# 4brar07_ESP8266.net
KiCad netlist of a schematic drawn in EAGLE
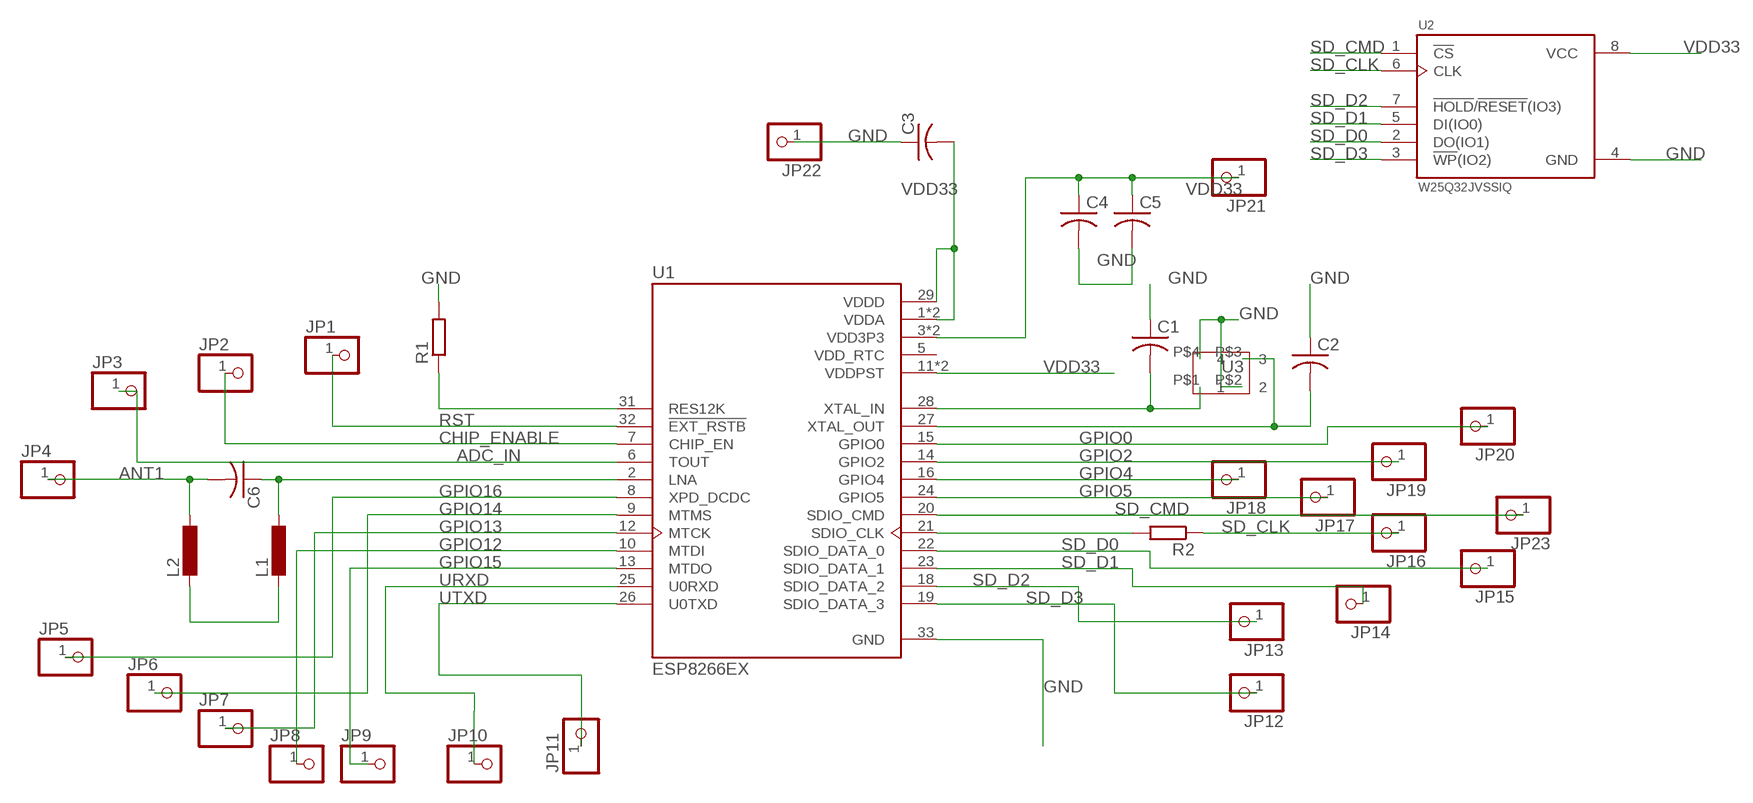
[diagram p0: schematic, sheet 1]

(export (version "E")
  (design (tool "Eeschema 10.0.6"))
  (components
    (comp (ref "C1")
      (value "C-USC0805")
      (footprint "eagle-import:C0805")
      (libsource (lib "eagle-import") (part "C-USC0805"))
    )
    (comp (ref "C2")
      (value "C-USC0805")
      (footprint "eagle-import:C0805")
      (libsource (lib "eagle-import") (part "C-USC0805"))
    )
    (comp (ref "C3")
      (value "C-USC0805")
      (footprint "eagle-import:C0805")
      (libsource (lib "eagle-import") (part "C-USC0805"))
    )
    (comp (ref "C4")
      (value "C-USC0805")
      (footprint "eagle-import:C0805")
      (libsource (lib "eagle-import") (part "C-USC0805"))
    )
    (comp (ref "C5")
      (value "C-USC0805")
      (footprint "eagle-import:C0805")
      (libsource (lib "eagle-import") (part "C-USC0805"))
    )
    (comp (ref "C6")
      (value "C-USC0805")
      (footprint "eagle-import:C0805")
      (libsource (lib "eagle-import") (part "C-USC0805"))
    )
    (comp (ref "JP1")
      (value "PINHD-1X1")
      (footprint "eagle-import:1X01")
      (libsource (lib "eagle-import") (part "PINHD-1X1"))
    )
    (comp (ref "JP2")
      (value "PINHD-1X1")
      (footprint "eagle-import:1X01")
      (libsource (lib "eagle-import") (part "PINHD-1X1"))
    )
    (comp (ref "JP3")
      (value "PINHD-1X1")
      (footprint "eagle-import:1X01")
      (libsource (lib "eagle-import") (part "PINHD-1X1"))
    )
    (comp (ref "JP4")
      (value "PINHD-1X1")
      (footprint "eagle-import:1X01")
      (libsource (lib "eagle-import") (part "PINHD-1X1"))
    )
    (comp (ref "JP5")
      (value "PINHD-1X1")
      (footprint "eagle-import:1X01")
      (libsource (lib "eagle-import") (part "PINHD-1X1"))
    )
    (comp (ref "JP6")
      (value "PINHD-1X1")
      (footprint "eagle-import:1X01")
      (libsource (lib "eagle-import") (part "PINHD-1X1"))
    )
    (comp (ref "JP7")
      (value "PINHD-1X1")
      (footprint "eagle-import:1X01")
      (libsource (lib "eagle-import") (part "PINHD-1X1"))
    )
    (comp (ref "JP8")
      (value "PINHD-1X1")
      (footprint "eagle-import:1X01")
      (libsource (lib "eagle-import") (part "PINHD-1X1"))
    )
    (comp (ref "JP9")
      (value "PINHD-1X1")
      (footprint "eagle-import:1X01")
      (libsource (lib "eagle-import") (part "PINHD-1X1"))
    )
    (comp (ref "JP10")
      (value "PINHD-1X1")
      (footprint "eagle-import:1X01")
      (libsource (lib "eagle-import") (part "PINHD-1X1"))
    )
    (comp (ref "JP11")
      (value "PINHD-1X1")
      (footprint "eagle-import:1X01")
      (libsource (lib "eagle-import") (part "PINHD-1X1"))
    )
    (comp (ref "JP12")
      (value "PINHD-1X1")
      (footprint "eagle-import:1X01")
      (libsource (lib "eagle-import") (part "PINHD-1X1"))
    )
    (comp (ref "JP13")
      (value "PINHD-1X1")
      (footprint "eagle-import:1X01")
      (libsource (lib "eagle-import") (part "PINHD-1X1"))
    )
    (comp (ref "JP14")
      (value "PINHD-1X1")
      (footprint "eagle-import:1X01")
      (libsource (lib "eagle-import") (part "PINHD-1X1"))
    )
    (comp (ref "JP15")
      (value "PINHD-1X1")
      (footprint "eagle-import:1X01")
      (libsource (lib "eagle-import") (part "PINHD-1X1"))
    )
    (comp (ref "JP16")
      (value "PINHD-1X1")
      (footprint "eagle-import:1X01")
      (libsource (lib "eagle-import") (part "PINHD-1X1"))
    )
    (comp (ref "JP17")
      (value "PINHD-1X1")
      (footprint "eagle-import:1X01")
      (libsource (lib "eagle-import") (part "PINHD-1X1"))
    )
    (comp (ref "JP18")
      (value "PINHD-1X1")
      (footprint "eagle-import:1X01")
      (libsource (lib "eagle-import") (part "PINHD-1X1"))
    )
    (comp (ref "JP19")
      (value "PINHD-1X1")
      (footprint "eagle-import:1X01")
      (libsource (lib "eagle-import") (part "PINHD-1X1"))
    )
    (comp (ref "JP20")
      (value "PINHD-1X1")
      (footprint "eagle-import:1X01")
      (libsource (lib "eagle-import") (part "PINHD-1X1"))
    )
    (comp (ref "JP21")
      (value "PINHD-1X1")
      (footprint "eagle-import:1X01")
      (libsource (lib "eagle-import") (part "PINHD-1X1"))
    )
    (comp (ref "JP22")
      (value "PINHD-1X1")
      (footprint "eagle-import:1X01")
      (libsource (lib "eagle-import") (part "PINHD-1X1"))
    )
    (comp (ref "JP23")
      (value "PINHD-1X1")
      (footprint "eagle-import:1X01")
      (libsource (lib "eagle-import") (part "PINHD-1X1"))
    )
    (comp (ref "L1")
      (value "L-EUL1812")
      (footprint "eagle-import:L1812")
      (libsource (lib "eagle-import") (part "L-EUL1812"))
    )
    (comp (ref "L2")
      (value "L-EUL1812")
      (footprint "eagle-import:L1812")
      (libsource (lib "eagle-import") (part "L-EUL1812"))
    )
    (comp (ref "R1")
      (value "R-EU_R0805")
      (footprint "eagle-import:R0805")
      (libsource (lib "eagle-import") (part "R-EU_R0805"))
    )
    (comp (ref "R2")
      (value "R-EU_R0805")
      (footprint "eagle-import:R0805")
      (libsource (lib "eagle-import") (part "R-EU_R0805"))
    )
    (comp (ref "U1")
      (value "ESP8266EX")
      (footprint "eagle-import:QFN50P500X500X80-33N")
      (fields (field (name "MF") "Espressif Systems"))
      (libsource (lib "eagle-import") (part "ESP8266EX"))
    )
    (comp (ref "U2")
      (value "W25Q32JVSSIQ")
      (footprint "eagle-import:SOIC127P790X216-8N")
      (fields (field (name "MF") "Winbond"))
      (libsource (lib "eagle-import") (part "W25Q32JVSSIQ"))
    )
    (comp (ref "U3")
      (value "Q22FA12800332")
      (footprint "eagle-import:OSCILLATOR")
      (fields (field (name "U3") "U3"))
      (libsource (lib "eagle-import") (part "Q22FA12800332"))
    )
  )
  (nets
    (net (code "1") (name "/ADC_IN") (class "Default")
      (node (ref "JP3") (pin "1") (pinfunction "1_1") (pintype "passive"))
      (node (ref "U1") (pin "6") (pinfunction "TOUT_6") (pintype "input"))
    )
    (net (code "2") (name "/ANT1") (class "Default")
      (node (ref "C6") (pin "2") (pinfunction "2_2") (pintype "passive"))
      (node (ref "JP4") (pin "1") (pinfunction "1_1") (pintype "passive"))
      (node (ref "L2") (pin "1") (pinfunction "1_1") (pintype "passive"))
    )
    (net (code "3") (name "/CHIP_ENABLE") (class "Default")
      (node (ref "JP2") (pin "1") (pinfunction "1_1") (pintype "passive"))
      (node (ref "U1") (pin "7") (pinfunction "CHIP_EN_7") (pintype "input"))
    )
    (net (code "4") (name "/GND") (class "Default")
      (node (ref "C1") (pin "1") (pinfunction "1_1") (pintype "passive"))
      (node (ref "C2") (pin "1") (pinfunction "1_1") (pintype "passive"))
      (node (ref "C3") (pin "1") (pinfunction "1_1") (pintype "passive"))
      (node (ref "C4") (pin "2") (pinfunction "2_2") (pintype "passive"))
      (node (ref "C5") (pin "2") (pinfunction "2_2") (pintype "passive"))
      (node (ref "JP22") (pin "1") (pinfunction "1_1") (pintype "passive"))
      (node (ref "R1") (pin "2") (pinfunction "2_2") (pintype "passive"))
      (node (ref "U1") (pin "33") (pinfunction "GND_33") (pintype "power_in"))
      (node (ref "U2") (pin "4") (pinfunction "GND_4") (pintype "power_in"))
      (node (ref "U3") (pin "P$2") (pinfunction "2_P$2") (pintype "bidirectional"))
      (node (ref "U3") (pin "P$4") (pinfunction "4_P$4") (pintype "bidirectional"))
    )
    (net (code "5") (name "/GPIO0") (class "Default")
      (node (ref "JP20") (pin "1") (pinfunction "1_1") (pintype "passive"))
      (node (ref "U1") (pin "15") (pinfunction "GPIO0_15") (pintype "bidirectional"))
    )
    (net (code "6") (name "/GPIO2") (class "Default")
      (node (ref "JP19") (pin "1") (pinfunction "1_1") (pintype "passive"))
      (node (ref "U1") (pin "14") (pinfunction "GPIO2_14") (pintype "bidirectional"))
    )
    (net (code "7") (name "/GPIO4") (class "Default")
      (node (ref "JP18") (pin "1") (pinfunction "1_1") (pintype "passive"))
      (node (ref "U1") (pin "16") (pinfunction "GPIO4_16") (pintype "bidirectional"))
    )
    (net (code "8") (name "/GPIO5") (class "Default")
      (node (ref "JP17") (pin "1") (pinfunction "1_1") (pintype "passive"))
      (node (ref "U1") (pin "24") (pinfunction "GPIO5_24") (pintype "bidirectional"))
    )
    (net (code "9") (name "/GPIO12") (class "Default")
      (node (ref "JP8") (pin "1") (pinfunction "1_1") (pintype "passive"))
      (node (ref "U1") (pin "10") (pinfunction "MTDI_10") (pintype "bidirectional"))
    )
    (net (code "10") (name "/GPIO13") (class "Default")
      (node (ref "JP7") (pin "1") (pinfunction "1_1") (pintype "passive"))
      (node (ref "U1") (pin "12") (pinfunction "MTCK_12") (pintype "bidirectional"))
    )
    (net (code "11") (name "/GPIO14") (class "Default")
      (node (ref "JP6") (pin "1") (pinfunction "1_1") (pintype "passive"))
      (node (ref "U1") (pin "9") (pinfunction "MTMS_9") (pintype "bidirectional"))
    )
    (net (code "12") (name "/GPIO15") (class "Default")
      (node (ref "JP9") (pin "1") (pinfunction "1_1") (pintype "passive"))
      (node (ref "U1") (pin "13") (pinfunction "MTDO_13") (pintype "bidirectional"))
    )
    (net (code "13") (name "/GPIO16") (class "Default")
      (node (ref "JP5") (pin "1") (pinfunction "1_1") (pintype "passive"))
      (node (ref "U1") (pin "8") (pinfunction "XPD_DCDC_8") (pintype "bidirectional"))
    )
    (net (code "14") (name "/RST") (class "Default")
      (node (ref "JP1") (pin "1") (pinfunction "1_1") (pintype "passive"))
      (node (ref "U1") (pin "32") (pinfunction "~{EXT_RSTB}_32") (pintype "input"))
    )
    (net (code "15") (name "/SD_CLK") (class "Default")
      (node (ref "JP16") (pin "1") (pinfunction "1_1") (pintype "passive"))
      (node (ref "R2") (pin "1") (pinfunction "1_1") (pintype "passive"))
      (node (ref "U2") (pin "6") (pinfunction "CLK_6") (pintype "input"))
    )
    (net (code "16") (name "/SD_CMD") (class "Default")
      (node (ref "JP23") (pin "1") (pinfunction "1_1") (pintype "passive"))
      (node (ref "U1") (pin "20") (pinfunction "SDIO_CMD_20") (pintype "bidirectional"))
      (node (ref "U2") (pin "1") (pinfunction "~{CS}_1") (pintype "input"))
    )
    (net (code "17") (name "/SD_D0") (class "Default")
      (node (ref "JP15") (pin "1") (pinfunction "1_1") (pintype "passive"))
      (node (ref "U1") (pin "22") (pinfunction "SDIO_DATA_0_22") (pintype "bidirectional"))
      (node (ref "U2") (pin "2") (pinfunction "DO(IO1)_2") (pintype "bidirectional"))
    )
    (net (code "18") (name "/SD_D1") (class "Default")
      (node (ref "JP14") (pin "1") (pinfunction "1_1") (pintype "passive"))
      (node (ref "U1") (pin "23") (pinfunction "SDIO_DATA_1_23") (pintype "bidirectional"))
      (node (ref "U2") (pin "5") (pinfunction "DI(IO0)_5") (pintype "bidirectional"))
    )
    (net (code "19") (name "/SD_D2") (class "Default")
      (node (ref "JP13") (pin "1") (pinfunction "1_1") (pintype "passive"))
      (node (ref "U1") (pin "18") (pinfunction "SDIO_DATA_2_18") (pintype "bidirectional"))
      (node (ref "U2") (pin "7") (pinfunction "~{HOLD}/~{RESET}(IO3)_7") (pintype "bidirectional"))
    )
    (net (code "20") (name "/SD_D3") (class "Default")
      (node (ref "JP12") (pin "1") (pinfunction "1_1") (pintype "passive"))
      (node (ref "U1") (pin "19") (pinfunction "SDIO_DATA_3_19") (pintype "bidirectional"))
      (node (ref "U2") (pin "3") (pinfunction "~{WP}(IO2)_3") (pintype "bidirectional"))
    )
    (net (code "21") (name "/URXD") (class "Default")
      (node (ref "JP10") (pin "1") (pinfunction "1_1") (pintype "passive"))
      (node (ref "U1") (pin "25") (pinfunction "U0RXD_25") (pintype "bidirectional"))
    )
    (net (code "22") (name "/UTXD") (class "Default")
      (node (ref "JP11") (pin "1") (pinfunction "1_1") (pintype "passive"))
      (node (ref "U1") (pin "26") (pinfunction "U0TXD_26") (pintype "bidirectional"))
    )
    (net (code "23") (name "/VDD33") (class "Default")
      (node (ref "C3") (pin "2") (pinfunction "2_2") (pintype "passive"))
      (node (ref "C4") (pin "1") (pinfunction "1_1") (pintype "passive"))
      (node (ref "C5") (pin "1") (pinfunction "1_1") (pintype "passive"))
      (node (ref "JP21") (pin "1") (pinfunction "1_1") (pintype "passive"))
      (node (ref "U1") (pin "1") (pinfunction "VDDA_1") (pintype "power_in"))
      (node (ref "U1") (pin "11") (pinfunction "VDDPST_11") (pintype "power_in"))
      (node (ref "U1") (pin "17") (pinfunction "VDDPST_17") (pintype "power_in"))
      (node (ref "U1") (pin "29") (pinfunction "VDDD_29") (pintype "power_in"))
      (node (ref "U1") (pin "3") (pinfunction "VDD3P3_3") (pintype "power_in"))
      (node (ref "U1") (pin "30") (pinfunction "VDDA_30") (pintype "power_in"))
      (node (ref "U1") (pin "4") (pinfunction "VDD3P3_4") (pintype "power_in"))
      (node (ref "U2") (pin "8") (pinfunction "VCC_8") (pintype "power_in"))
    )
    (net (code "24") (name "/VDD_RTC") (class "Default")
      (node (ref "U1") (pin "5") (pinfunction "VDD_RTC_5") (pintype "power_in"))
    )
    (net (code "25") (name "Net-(L1-Pad2)") (class "Default")
      (node (ref "L1") (pin "2") (pinfunction "2_2") (pintype "passive"))
      (node (ref "L2") (pin "2") (pinfunction "2_2") (pintype "passive"))
    )
    (net (code "26") (name "Net-(U1-LNA)") (class "Default")
      (node (ref "C6") (pin "1") (pinfunction "1_1") (pintype "passive"))
      (node (ref "L1") (pin "1") (pinfunction "1_1") (pintype "passive"))
      (node (ref "U1") (pin "2") (pinfunction "LNA_2") (pintype "bidirectional"))
    )
    (net (code "27") (name "Net-(U1-RES12K)") (class "Default")
      (node (ref "R1") (pin "1") (pinfunction "1_1") (pintype "passive"))
      (node (ref "U1") (pin "31") (pinfunction "RES12K_31") (pintype "input"))
    )
    (net (code "28") (name "Net-(U1-SDIO_CLK)") (class "Default")
      (node (ref "R2") (pin "2") (pinfunction "2_2") (pintype "passive"))
      (node (ref "U1") (pin "21") (pinfunction "SDIO_CLK_21") (pintype "bidirectional"))
    )
    (net (code "29") (name "Net-(U1-XTAL_IN)") (class "Default")
      (node (ref "C1") (pin "2") (pinfunction "2_2") (pintype "passive"))
      (node (ref "U1") (pin "28") (pinfunction "XTAL_IN_28") (pintype "bidirectional"))
      (node (ref "U3") (pin "P$1") (pinfunction "1_P$1") (pintype "bidirectional"))
    )
    (net (code "30") (name "Net-(U1-XTAL_OUT)") (class "Default")
      (node (ref "C2") (pin "2") (pinfunction "2_2") (pintype "passive"))
      (node (ref "U1") (pin "27") (pinfunction "XTAL_OUT_27") (pintype "bidirectional"))
      (node (ref "U3") (pin "P$3") (pinfunction "3_P$3") (pintype "bidirectional"))
    )
  )
)
